# m1-data-register-b.net
KiCad netlist of a schematic drawn in EAGLE
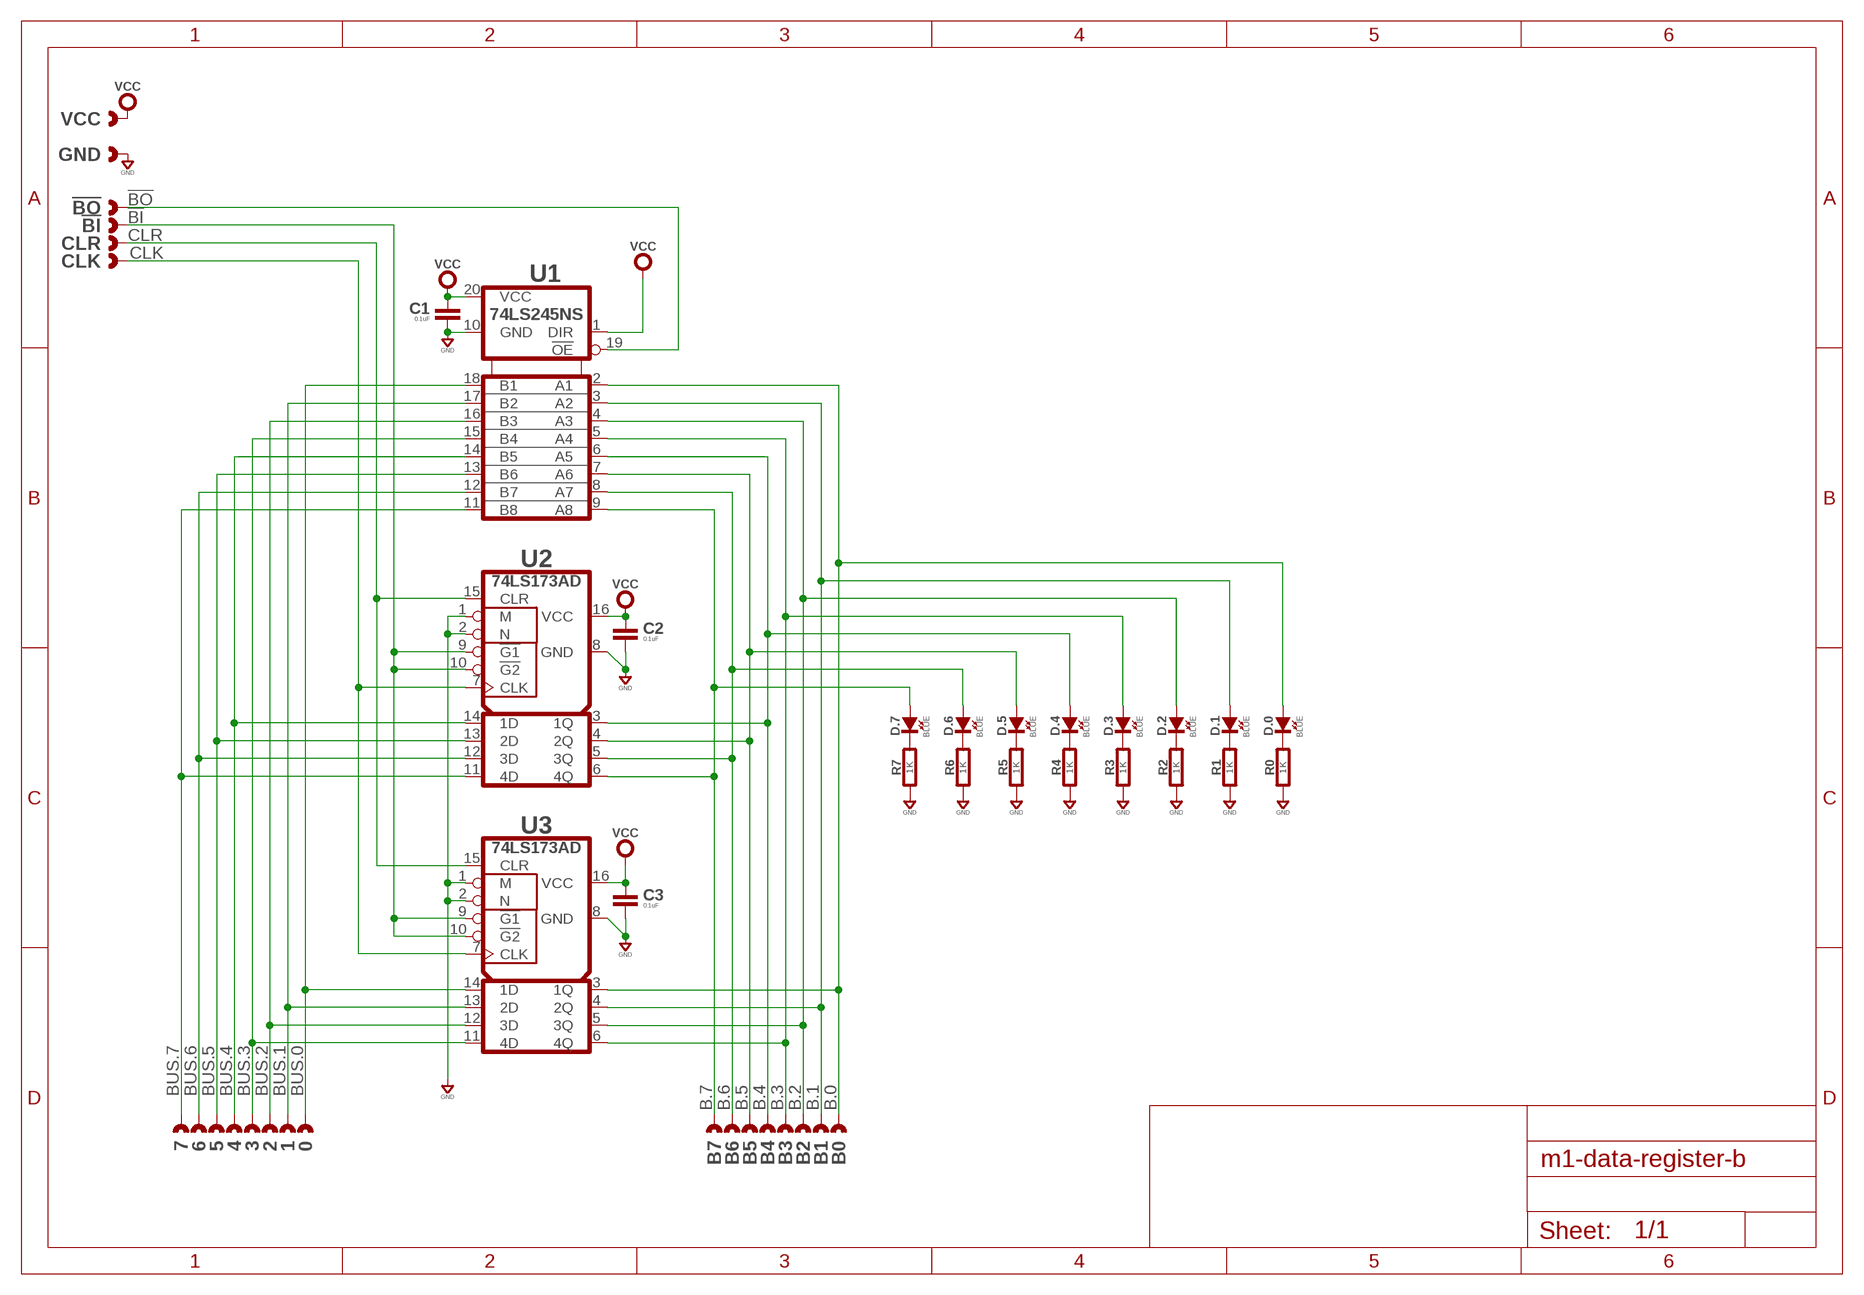
[diagram p0: schematic, sheet 1]

(export (version "E")
  (design (tool "Eeschema 10.0.6"))
  (components
    (comp (ref "!BI")
      (value "CAST-01X1")
      (footprint "eagle-import:CAST01-2.54MM")
      (libsource (lib "eagle-import") (part "CAST-01X1"))
    )
    (comp (ref "!BO")
      (value "CAST-01X1")
      (footprint "eagle-import:CAST01-2.54MM")
      (libsource (lib "eagle-import") (part "CAST-01X1"))
    )
    (comp (ref "0")
      (value "CAST-01X1")
      (footprint "eagle-import:CAST01-2.54MM")
      (libsource (lib "eagle-import") (part "CAST-01X1"))
    )
    (comp (ref "1")
      (value "CAST-01X1")
      (footprint "eagle-import:CAST01-2.54MM")
      (libsource (lib "eagle-import") (part "CAST-01X1"))
    )
    (comp (ref "2")
      (value "CAST-01X1")
      (footprint "eagle-import:CAST01-2.54MM")
      (libsource (lib "eagle-import") (part "CAST-01X1"))
    )
    (comp (ref "3")
      (value "CAST-01X1")
      (footprint "eagle-import:CAST01-2.54MM")
      (libsource (lib "eagle-import") (part "CAST-01X1"))
    )
    (comp (ref "4")
      (value "CAST-01X1")
      (footprint "eagle-import:CAST01-2.54MM")
      (libsource (lib "eagle-import") (part "CAST-01X1"))
    )
    (comp (ref "5")
      (value "CAST-01X1")
      (footprint "eagle-import:CAST01-2.54MM")
      (libsource (lib "eagle-import") (part "CAST-01X1"))
    )
    (comp (ref "6")
      (value "CAST-01X1")
      (footprint "eagle-import:CAST01-2.54MM")
      (libsource (lib "eagle-import") (part "CAST-01X1"))
    )
    (comp (ref "7")
      (value "CAST-01X1")
      (footprint "eagle-import:CAST01-2.54MM")
      (libsource (lib "eagle-import") (part "CAST-01X1"))
    )
    (comp (ref "B0")
      (value "CAST-01X1")
      (footprint "eagle-import:CAST01-2.54MM")
      (libsource (lib "eagle-import") (part "CAST-01X1"))
    )
    (comp (ref "B1")
      (value "CAST-01X1")
      (footprint "eagle-import:CAST01-2.54MM")
      (libsource (lib "eagle-import") (part "CAST-01X1"))
    )
    (comp (ref "B2")
      (value "CAST-01X1")
      (footprint "eagle-import:CAST01-2.54MM")
      (libsource (lib "eagle-import") (part "CAST-01X1"))
    )
    (comp (ref "B3")
      (value "CAST-01X1")
      (footprint "eagle-import:CAST01-2.54MM")
      (libsource (lib "eagle-import") (part "CAST-01X1"))
    )
    (comp (ref "B4")
      (value "CAST-01X1")
      (footprint "eagle-import:CAST01-2.54MM")
      (libsource (lib "eagle-import") (part "CAST-01X1"))
    )
    (comp (ref "B5")
      (value "CAST-01X1")
      (footprint "eagle-import:CAST01-2.54MM")
      (libsource (lib "eagle-import") (part "CAST-01X1"))
    )
    (comp (ref "B6")
      (value "CAST-01X1")
      (footprint "eagle-import:CAST01-2.54MM")
      (libsource (lib "eagle-import") (part "CAST-01X1"))
    )
    (comp (ref "B7")
      (value "CAST-01X1")
      (footprint "eagle-import:CAST01-2.54MM")
      (libsource (lib "eagle-import") (part "CAST-01X1"))
    )
    (comp (ref "C1")
      (value "0.1uF")
      (footprint "eagle-import:0603-CAP")
      (libsource (lib "eagle-import") (part "CAPACITOR0603"))
    )
    (comp (ref "C2")
      (value "0.1uF")
      (footprint "eagle-import:0603-CAP")
      (libsource (lib "eagle-import") (part "CAPACITOR0603"))
    )
    (comp (ref "C3")
      (value "0.1uF")
      (footprint "eagle-import:0603-CAP")
      (libsource (lib "eagle-import") (part "CAPACITOR0603"))
    )
    (comp (ref "CLK")
      (value "CAST-01X1")
      (footprint "eagle-import:CAST01-2.54MM")
      (libsource (lib "eagle-import") (part "CAST-01X1"))
    )
    (comp (ref "CLR")
      (value "CAST-01X1")
      (footprint "eagle-import:CAST01-2.54MM")
      (libsource (lib "eagle-import") (part "CAST-01X1"))
    )
    (comp (ref "D.0")
      (value "BLUE")
      (footprint "eagle-import:SMD_0603")
      (libsource (lib "eagle-import") (part "SMT0603"))
    )
    (comp (ref "D.1")
      (value "BLUE")
      (footprint "eagle-import:SMD_0603")
      (libsource (lib "eagle-import") (part "SMT0603"))
    )
    (comp (ref "D.2")
      (value "BLUE")
      (footprint "eagle-import:SMD_0603")
      (libsource (lib "eagle-import") (part "SMT0603"))
    )
    (comp (ref "D.3")
      (value "BLUE")
      (footprint "eagle-import:SMD_0603")
      (libsource (lib "eagle-import") (part "SMT0603"))
    )
    (comp (ref "D.4")
      (value "BLUE")
      (footprint "eagle-import:SMD_0603")
      (libsource (lib "eagle-import") (part "SMT0603"))
    )
    (comp (ref "D.5")
      (value "BLUE")
      (footprint "eagle-import:SMD_0603")
      (libsource (lib "eagle-import") (part "SMT0603"))
    )
    (comp (ref "D.6")
      (value "BLUE")
      (footprint "eagle-import:SMD_0603")
      (libsource (lib "eagle-import") (part "SMT0603"))
    )
    (comp (ref "D.7")
      (value "BLUE")
      (footprint "eagle-import:SMD_0603")
      (libsource (lib "eagle-import") (part "SMT0603"))
    )
    (comp (ref "GND")
      (value "CAST-01X1")
      (footprint "eagle-import:CAST01-2.54MM")
      (libsource (lib "eagle-import") (part "CAST-01X1"))
    )
    (comp (ref "R0")
      (value "1K")
      (footprint "eagle-import:0603-RES")
      (libsource (lib "eagle-import") (part "RESISTOR0603"))
    )
    (comp (ref "R1")
      (value "1K")
      (footprint "eagle-import:0603-RES")
      (libsource (lib "eagle-import") (part "RESISTOR0603"))
    )
    (comp (ref "R2")
      (value "1K")
      (footprint "eagle-import:0603-RES")
      (libsource (lib "eagle-import") (part "RESISTOR0603"))
    )
    (comp (ref "R3")
      (value "1K")
      (footprint "eagle-import:0603-RES")
      (libsource (lib "eagle-import") (part "RESISTOR0603"))
    )
    (comp (ref "R4")
      (value "1K")
      (footprint "eagle-import:0603-RES")
      (libsource (lib "eagle-import") (part "RESISTOR0603"))
    )
    (comp (ref "R5")
      (value "1K")
      (footprint "eagle-import:0603-RES")
      (libsource (lib "eagle-import") (part "RESISTOR0603"))
    )
    (comp (ref "R6")
      (value "1K")
      (footprint "eagle-import:0603-RES")
      (libsource (lib "eagle-import") (part "RESISTOR0603"))
    )
    (comp (ref "R7")
      (value "1K")
      (footprint "eagle-import:0603-RES")
      (libsource (lib "eagle-import") (part "RESISTOR0603"))
    )
    (comp (ref "U1")
      (value "74LS245NS")
      (footprint "eagle-import:SO20")
      (libsource (lib "eagle-import") (part "74245?NSLS"))
    )
    (comp (ref "U2")
      (value "74LS173AD")
      (footprint "eagle-import:SO16")
      (libsource (lib "eagle-import") (part "74173A?DLS"))
    )
    (comp (ref "U3")
      (value "74LS173AD")
      (footprint "eagle-import:SO16")
      (libsource (lib "eagle-import") (part "74173A?DLS"))
    )
    (comp (ref "VCC")
      (value "CAST-01X1")
      (footprint "eagle-import:CAST01-2.54MM")
      (libsource (lib "eagle-import") (part "CAST-01X1"))
    )
  )
  (nets
    (net (code "1") (name "/B.0") (class "Default")
      (node (ref "B0") (pin "1") (pinfunction "1_1") (pintype "bidirectional"))
      (node (ref "D.0") (pin "A") (pinfunction "A_A") (pintype "passive"))
      (node (ref "U1") (pin "2") (pinfunction "A1_2") (pintype "bidirectional"))
      (node (ref "U3") (pin "3") (pinfunction "1Q_3") (pintype "bidirectional"))
    )
    (net (code "2") (name "/B.1") (class "Default")
      (node (ref "B1") (pin "1") (pinfunction "1_1") (pintype "bidirectional"))
      (node (ref "D.1") (pin "A") (pinfunction "A_A") (pintype "passive"))
      (node (ref "U1") (pin "3") (pinfunction "A2_3") (pintype "bidirectional"))
      (node (ref "U3") (pin "4") (pinfunction "2Q_4") (pintype "bidirectional"))
    )
    (net (code "3") (name "/B.2") (class "Default")
      (node (ref "B2") (pin "1") (pinfunction "1_1") (pintype "bidirectional"))
      (node (ref "D.2") (pin "A") (pinfunction "A_A") (pintype "passive"))
      (node (ref "U1") (pin "4") (pinfunction "A3_4") (pintype "bidirectional"))
      (node (ref "U3") (pin "5") (pinfunction "3Q_5") (pintype "bidirectional"))
    )
    (net (code "4") (name "/B.3") (class "Default")
      (node (ref "B3") (pin "1") (pinfunction "1_1") (pintype "bidirectional"))
      (node (ref "D.3") (pin "A") (pinfunction "A_A") (pintype "passive"))
      (node (ref "U1") (pin "5") (pinfunction "A4_5") (pintype "bidirectional"))
      (node (ref "U3") (pin "6") (pinfunction "4Q_6") (pintype "bidirectional"))
    )
    (net (code "5") (name "/B.4") (class "Default")
      (node (ref "B4") (pin "1") (pinfunction "1_1") (pintype "bidirectional"))
      (node (ref "D.4") (pin "A") (pinfunction "A_A") (pintype "passive"))
      (node (ref "U1") (pin "6") (pinfunction "A5_6") (pintype "bidirectional"))
      (node (ref "U2") (pin "3") (pinfunction "1Q_3") (pintype "bidirectional"))
    )
    (net (code "6") (name "/B.5") (class "Default")
      (node (ref "B5") (pin "1") (pinfunction "1_1") (pintype "bidirectional"))
      (node (ref "D.5") (pin "A") (pinfunction "A_A") (pintype "passive"))
      (node (ref "U1") (pin "7") (pinfunction "A6_7") (pintype "bidirectional"))
      (node (ref "U2") (pin "4") (pinfunction "2Q_4") (pintype "bidirectional"))
    )
    (net (code "7") (name "/B.6") (class "Default")
      (node (ref "B6") (pin "1") (pinfunction "1_1") (pintype "bidirectional"))
      (node (ref "D.6") (pin "A") (pinfunction "A_A") (pintype "passive"))
      (node (ref "U1") (pin "8") (pinfunction "A7_8") (pintype "bidirectional"))
      (node (ref "U2") (pin "5") (pinfunction "3Q_5") (pintype "bidirectional"))
    )
    (net (code "8") (name "/B.7") (class "Default")
      (node (ref "B7") (pin "1") (pinfunction "1_1") (pintype "bidirectional"))
      (node (ref "D.7") (pin "A") (pinfunction "A_A") (pintype "passive"))
      (node (ref "U1") (pin "9") (pinfunction "A8_9") (pintype "bidirectional"))
      (node (ref "U2") (pin "6") (pinfunction "4Q_6") (pintype "bidirectional"))
    )
    (net (code "9") (name "/BUS.0") (class "Default")
      (node (ref "0") (pin "1") (pinfunction "1_1") (pintype "bidirectional"))
      (node (ref "U1") (pin "18") (pinfunction "B1_18") (pintype "bidirectional"))
      (node (ref "U3") (pin "14") (pinfunction "1D_14") (pintype "bidirectional"))
    )
    (net (code "10") (name "/BUS.1") (class "Default")
      (node (ref "1") (pin "1") (pinfunction "1_1") (pintype "bidirectional"))
      (node (ref "U1") (pin "17") (pinfunction "B2_17") (pintype "bidirectional"))
      (node (ref "U3") (pin "13") (pinfunction "2D_13") (pintype "bidirectional"))
    )
    (net (code "11") (name "/BUS.2") (class "Default")
      (node (ref "2") (pin "1") (pinfunction "1_1") (pintype "bidirectional"))
      (node (ref "U1") (pin "16") (pinfunction "B3_16") (pintype "bidirectional"))
      (node (ref "U3") (pin "12") (pinfunction "3D_12") (pintype "bidirectional"))
    )
    (net (code "12") (name "/BUS.3") (class "Default")
      (node (ref "3") (pin "1") (pinfunction "1_1") (pintype "bidirectional"))
      (node (ref "U1") (pin "15") (pinfunction "B4_15") (pintype "bidirectional"))
      (node (ref "U3") (pin "11") (pinfunction "4D_11") (pintype "bidirectional"))
    )
    (net (code "13") (name "/BUS.4") (class "Default")
      (node (ref "4") (pin "1") (pinfunction "1_1") (pintype "bidirectional"))
      (node (ref "U1") (pin "14") (pinfunction "B5_14") (pintype "bidirectional"))
      (node (ref "U2") (pin "14") (pinfunction "1D_14") (pintype "bidirectional"))
    )
    (net (code "14") (name "/BUS.5") (class "Default")
      (node (ref "5") (pin "1") (pinfunction "1_1") (pintype "bidirectional"))
      (node (ref "U1") (pin "13") (pinfunction "B6_13") (pintype "bidirectional"))
      (node (ref "U2") (pin "13") (pinfunction "2D_13") (pintype "bidirectional"))
    )
    (net (code "15") (name "/BUS.6") (class "Default")
      (node (ref "6") (pin "1") (pinfunction "1_1") (pintype "bidirectional"))
      (node (ref "U1") (pin "12") (pinfunction "B7_12") (pintype "bidirectional"))
      (node (ref "U2") (pin "12") (pinfunction "3D_12") (pintype "bidirectional"))
    )
    (net (code "16") (name "/BUS.7") (class "Default")
      (node (ref "7") (pin "1") (pinfunction "1_1") (pintype "bidirectional"))
      (node (ref "U1") (pin "11") (pinfunction "B8_11") (pintype "bidirectional"))
      (node (ref "U2") (pin "11") (pinfunction "4D_11") (pintype "bidirectional"))
    )
    (net (code "17") (name "/CLK") (class "Default")
      (node (ref "CLK") (pin "1") (pinfunction "1_1") (pintype "bidirectional"))
      (node (ref "U2") (pin "7") (pinfunction "CLK_7") (pintype "bidirectional"))
      (node (ref "U3") (pin "7") (pinfunction "CLK_7") (pintype "bidirectional"))
    )
    (net (code "18") (name "/CLR") (class "Default")
      (node (ref "CLR") (pin "1") (pinfunction "1_1") (pintype "bidirectional"))
      (node (ref "U2") (pin "15") (pinfunction "CLR_15") (pintype "bidirectional"))
      (node (ref "U3") (pin "15") (pinfunction "CLR_15") (pintype "bidirectional"))
    )
    (net (code "19") (name "/~{BI}") (class "Default")
      (node (ref "!BI") (pin "1") (pinfunction "1_1") (pintype "bidirectional"))
      (node (ref "U2") (pin "10") (pinfunction "~{G2}_10") (pintype "bidirectional"))
      (node (ref "U2") (pin "9") (pinfunction "~{G1}_9") (pintype "bidirectional"))
      (node (ref "U3") (pin "10") (pinfunction "~{G2}_10") (pintype "bidirectional"))
      (node (ref "U3") (pin "9") (pinfunction "~{G1}_9") (pintype "bidirectional"))
    )
    (net (code "20") (name "/~{BO}") (class "Default")
      (node (ref "!BO") (pin "1") (pinfunction "1_1") (pintype "bidirectional"))
      (node (ref "U1") (pin "19") (pinfunction "~{OE}_19") (pintype "bidirectional"))
    )
    (net (code "21") (name "GND") (class "Default")
      (node (ref "C1") (pin "2") (pinfunction "2_2") (pintype "passive"))
      (node (ref "C2") (pin "2") (pinfunction "2_2") (pintype "passive"))
      (node (ref "C3") (pin "2") (pinfunction "2_2") (pintype "passive"))
      (node (ref "GND") (pin "1") (pinfunction "1_1") (pintype "bidirectional"))
      (node (ref "R0") (pin "1") (pinfunction "1_1") (pintype "passive"))
      (node (ref "R1") (pin "1") (pinfunction "1_1") (pintype "passive"))
      (node (ref "R2") (pin "1") (pinfunction "1_1") (pintype "passive"))
      (node (ref "R3") (pin "1") (pinfunction "1_1") (pintype "passive"))
      (node (ref "R4") (pin "1") (pinfunction "1_1") (pintype "passive"))
      (node (ref "R5") (pin "1") (pinfunction "1_1") (pintype "passive"))
      (node (ref "R6") (pin "1") (pinfunction "1_1") (pintype "passive"))
      (node (ref "R7") (pin "1") (pinfunction "1_1") (pintype "passive"))
      (node (ref "U1") (pin "10") (pinfunction "GND_10") (pintype "bidirectional"))
      (node (ref "U2") (pin "1") (pinfunction "M_1") (pintype "bidirectional"))
      (node (ref "U2") (pin "2") (pinfunction "N_2") (pintype "bidirectional"))
      (node (ref "U2") (pin "8") (pinfunction "GND_8") (pintype "bidirectional"))
      (node (ref "U3") (pin "1") (pinfunction "M_1") (pintype "bidirectional"))
      (node (ref "U3") (pin "2") (pinfunction "N_2") (pintype "bidirectional"))
      (node (ref "U3") (pin "8") (pinfunction "GND_8") (pintype "bidirectional"))
    )
    (net (code "22") (name "Net-(D.0-C)") (class "Default")
      (node (ref "D.0") (pin "K") (pinfunction "C_K") (pintype "passive"))
      (node (ref "R0") (pin "2") (pinfunction "2_2") (pintype "passive"))
    )
    (net (code "23") (name "Net-(D.1-C)") (class "Default")
      (node (ref "D.1") (pin "K") (pinfunction "C_K") (pintype "passive"))
      (node (ref "R1") (pin "2") (pinfunction "2_2") (pintype "passive"))
    )
    (net (code "24") (name "Net-(D.2-C)") (class "Default")
      (node (ref "D.2") (pin "K") (pinfunction "C_K") (pintype "passive"))
      (node (ref "R2") (pin "2") (pinfunction "2_2") (pintype "passive"))
    )
    (net (code "25") (name "Net-(D.3-C)") (class "Default")
      (node (ref "D.3") (pin "K") (pinfunction "C_K") (pintype "passive"))
      (node (ref "R3") (pin "2") (pinfunction "2_2") (pintype "passive"))
    )
    (net (code "26") (name "Net-(D.4-C)") (class "Default")
      (node (ref "D.4") (pin "K") (pinfunction "C_K") (pintype "passive"))
      (node (ref "R4") (pin "2") (pinfunction "2_2") (pintype "passive"))
    )
    (net (code "27") (name "Net-(D.5-C)") (class "Default")
      (node (ref "D.5") (pin "K") (pinfunction "C_K") (pintype "passive"))
      (node (ref "R5") (pin "2") (pinfunction "2_2") (pintype "passive"))
    )
    (net (code "28") (name "Net-(D.6-C)") (class "Default")
      (node (ref "D.6") (pin "K") (pinfunction "C_K") (pintype "passive"))
      (node (ref "R6") (pin "2") (pinfunction "2_2") (pintype "passive"))
    )
    (net (code "29") (name "Net-(D.7-C)") (class "Default")
      (node (ref "D.7") (pin "K") (pinfunction "C_K") (pintype "passive"))
      (node (ref "R7") (pin "2") (pinfunction "2_2") (pintype "passive"))
    )
    (net (code "30") (name "VCC") (class "Default")
      (node (ref "C1") (pin "1") (pinfunction "1_1") (pintype "passive"))
      (node (ref "C2") (pin "1") (pinfunction "1_1") (pintype "passive"))
      (node (ref "C3") (pin "1") (pinfunction "1_1") (pintype "passive"))
      (node (ref "U1") (pin "1") (pinfunction "DIR_1") (pintype "bidirectional"))
      (node (ref "U1") (pin "20") (pinfunction "VCC_20") (pintype "bidirectional"))
      (node (ref "U2") (pin "16") (pinfunction "VCC_16") (pintype "bidirectional"))
      (node (ref "U3") (pin "16") (pinfunction "VCC_16") (pintype "bidirectional"))
      (node (ref "VCC") (pin "1") (pinfunction "1_1") (pintype "bidirectional"))
    )
  )
)
